# RatDBS.net
KiCad netlist of a schematic drawn in EAGLE
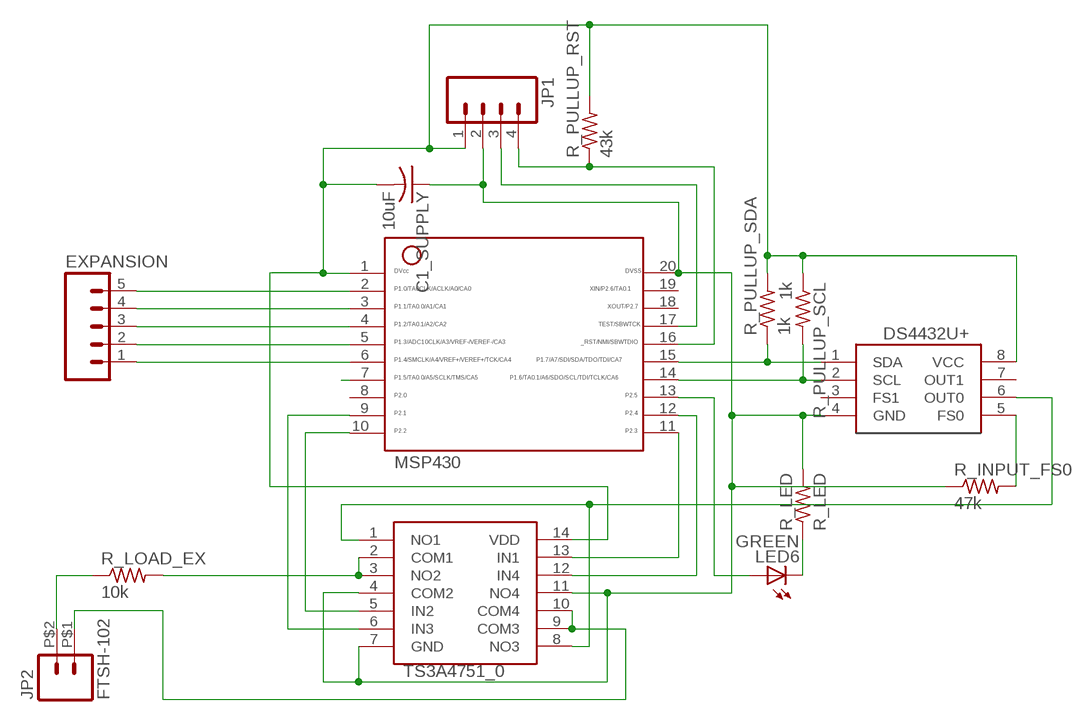
[diagram p0: schematic, sheet 1]

(export (version "E")
  (design (tool "Eeschema 10.0.6"))
  (components
    (comp (ref "C1_SUPPLY")
      (value "10uF")
      (footprint "eagle-import:C0603")
      (libsource (lib "eagle-import") (part "C-USC0603"))
    )
    (comp (ref "DS4432U+")
      (value "DS4432U+")
      (footprint "eagle-import:8_PIN")
      (libsource (lib "eagle-import") (part "DS4432U+"))
    )
    (comp (ref "EXPANSION")
      (value "M051.27MM")
      (footprint "eagle-import:1X05-1.27MM")
      (libsource (lib "eagle-import") (part "M051.27MM"))
    )
    (comp (ref "JP1")
      (value "M041.27MM")
      (footprint "eagle-import:1X04-1.27MM")
      (libsource (lib "eagle-import") (part "M041.27MM"))
    )
    (comp (ref "JP2")
      (value "FTSH-102")
      (footprint "eagle-import:FTSH-102-DH")
      (libsource (lib "eagle-import") (part "FTSH-102"))
    )
    (comp (ref "LED6")
      (value "GREEN")
      (footprint "eagle-import:LED-1206")
      (libsource (lib "eagle-import") (part "LED1206"))
    )
    (comp (ref "MSP430")
      (value "MSP430")
      (footprint "eagle-import:20_PIN")
      (libsource (lib "eagle-import") (part "MSP430"))
    )
    (comp (ref "R_INPUT_FS0")
      (value "47k")
      (footprint "eagle-import:R0603")
      (libsource (lib "eagle-import") (part "R-US_R0603"))
    )
    (comp (ref "R_LED")
      (value "R_LED")
      (footprint "eagle-import:R0603")
      (libsource (lib "eagle-import") (part "R-US_R0603"))
    )
    (comp (ref "R_LOAD_EX")
      (value "10k")
      (footprint "eagle-import:R0603")
      (libsource (lib "eagle-import") (part "R-US_R0603"))
    )
    (comp (ref "R_PULLUP_RST")
      (value "43k")
      (footprint "eagle-import:R0603")
      (libsource (lib "eagle-import") (part "R-US_R0603"))
    )
    (comp (ref "R_PULLUP_SCL")
      (value "1k")
      (footprint "eagle-import:R0603")
      (libsource (lib "eagle-import") (part "R-US_R0603"))
    )
    (comp (ref "R_PULLUP_SDA")
      (value "1k")
      (footprint "eagle-import:R0603")
      (libsource (lib "eagle-import") (part "R-US_R0603"))
    )
    (comp (ref "TS3A4751_0")
      (value "TS3A4751")
      (footprint "eagle-import:14_PIN")
      (libsource (lib "eagle-import") (part "TS3A4751"))
    )
  )
  (nets
    (net (code "1") (name "Net-(DS4432U+-FS0)") (class "Default")
      (node (ref "DS4432U+") (pin "5") (pinfunction "FS0_5") (pintype "bidirectional"))
      (node (ref "R_INPUT_FS0") (pin "2") (pinfunction "2_2") (pintype "passive"))
    )
    (net (code "2") (name "Net-(DS4432U+-GND)") (class "Default")
      (node (ref "C1_SUPPLY") (pin "1") (pinfunction "1_1") (pintype "passive"))
      (node (ref "DS4432U+") (pin "4") (pinfunction "GND_4") (pintype "bidirectional"))
      (node (ref "JP1") (pin "2") (pinfunction "2_2") (pintype "passive"))
      (node (ref "MSP430") (pin "20") (pinfunction "20_20") (pintype "bidirectional"))
      (node (ref "R_INPUT_FS0") (pin "1") (pinfunction "1_1") (pintype "passive"))
      (node (ref "R_LED") (pin "2") (pinfunction "2_2") (pintype "passive"))
      (node (ref "TS3A4751_0") (pin "11") (pinfunction "NO4_11") (pintype "bidirectional"))
      (node (ref "TS3A4751_0") (pin "4") (pinfunction "COM2_4") (pintype "bidirectional"))
      (node (ref "TS3A4751_0") (pin "7") (pinfunction "GND_7") (pintype "bidirectional"))
    )
    (net (code "3") (name "Net-(DS4432U+-OUT0)") (class "Default")
      (node (ref "DS4432U+") (pin "6") (pinfunction "OUT0_6") (pintype "bidirectional"))
      (node (ref "TS3A4751_0") (pin "1") (pinfunction "NO1_1") (pintype "bidirectional"))
      (node (ref "TS3A4751_0") (pin "8") (pinfunction "NO3_8") (pintype "bidirectional"))
    )
    (net (code "4") (name "Net-(DS4432U+-SCL)") (class "Default")
      (node (ref "DS4432U+") (pin "2") (pinfunction "SCL_2") (pintype "bidirectional"))
      (node (ref "MSP430") (pin "14") (pinfunction "14_14") (pintype "bidirectional"))
      (node (ref "R_PULLUP_SCL") (pin "2") (pinfunction "2_2") (pintype "passive"))
    )
    (net (code "5") (name "Net-(DS4432U+-SDA)") (class "Default")
      (node (ref "DS4432U+") (pin "1") (pinfunction "SDA_1") (pintype "bidirectional"))
      (node (ref "MSP430") (pin "15") (pinfunction "15_15") (pintype "bidirectional"))
      (node (ref "R_PULLUP_SDA") (pin "1") (pinfunction "1_1") (pintype "passive"))
    )
    (net (code "6") (name "Net-(DS4432U+-VCC)") (class "Default")
      (node (ref "C1_SUPPLY") (pin "2") (pinfunction "2_2") (pintype "passive"))
      (node (ref "DS4432U+") (pin "8") (pinfunction "VCC_8") (pintype "bidirectional"))
      (node (ref "JP1") (pin "1") (pinfunction "1_1") (pintype "passive"))
      (node (ref "MSP430") (pin "1") (pinfunction "1_1") (pintype "bidirectional"))
      (node (ref "R_PULLUP_RST") (pin "2") (pinfunction "2_2") (pintype "passive"))
      (node (ref "R_PULLUP_SCL") (pin "1") (pinfunction "1_1") (pintype "passive"))
      (node (ref "R_PULLUP_SDA") (pin "2") (pinfunction "2_2") (pintype "passive"))
      (node (ref "TS3A4751_0") (pin "14") (pinfunction "VDD_14") (pintype "bidirectional"))
    )
    (net (code "7") (name "Net-(EXPANSION-Pad1)") (class "Default")
      (node (ref "EXPANSION") (pin "1") (pinfunction "1_1") (pintype "passive"))
      (node (ref "MSP430") (pin "6") (pinfunction "6_6") (pintype "bidirectional"))
    )
    (net (code "8") (name "Net-(EXPANSION-Pad2)") (class "Default")
      (node (ref "EXPANSION") (pin "2") (pinfunction "2_2") (pintype "passive"))
      (node (ref "MSP430") (pin "5") (pinfunction "5_5") (pintype "bidirectional"))
    )
    (net (code "9") (name "Net-(EXPANSION-Pad3)") (class "Default")
      (node (ref "EXPANSION") (pin "3") (pinfunction "3_3") (pintype "passive"))
      (node (ref "MSP430") (pin "4") (pinfunction "4_4") (pintype "bidirectional"))
    )
    (net (code "10") (name "Net-(EXPANSION-Pad4)") (class "Default")
      (node (ref "EXPANSION") (pin "4") (pinfunction "4_4") (pintype "passive"))
      (node (ref "MSP430") (pin "3") (pinfunction "3_3") (pintype "bidirectional"))
    )
    (net (code "11") (name "Net-(EXPANSION-Pad5)") (class "Default")
      (node (ref "EXPANSION") (pin "5") (pinfunction "5_5") (pintype "passive"))
      (node (ref "MSP430") (pin "2") (pinfunction "2_2") (pintype "bidirectional"))
    )
    (net (code "12") (name "Net-(JP1-Pad3)") (class "Default")
      (node (ref "JP1") (pin "3") (pinfunction "3_3") (pintype "passive"))
      (node (ref "MSP430") (pin "17") (pinfunction "17_17") (pintype "bidirectional"))
    )
    (net (code "13") (name "Net-(JP1-Pad4)") (class "Default")
      (node (ref "JP1") (pin "4") (pinfunction "4_4") (pintype "passive"))
      (node (ref "MSP430") (pin "16") (pinfunction "16_16") (pintype "bidirectional"))
      (node (ref "R_PULLUP_RST") (pin "1") (pinfunction "1_1") (pintype "passive"))
    )
    (net (code "14") (name "Net-(JP2-1)") (class "Default")
      (node (ref "JP2") (pin "P$1") (pinfunction "1_P$1") (pintype "passive"))
      (node (ref "TS3A4751_0") (pin "10") (pinfunction "COM4_10") (pintype "bidirectional"))
      (node (ref "TS3A4751_0") (pin "9") (pinfunction "COM3_9") (pintype "bidirectional"))
    )
    (net (code "15") (name "Net-(JP2-2)") (class "Default")
      (node (ref "JP2") (pin "P$2") (pinfunction "2_P$2") (pintype "passive"))
      (node (ref "R_LOAD_EX") (pin "1") (pinfunction "1_1") (pintype "passive"))
    )
    (net (code "16") (name "Net-(LED6-PadA)") (class "Default")
      (node (ref "LED6") (pin "A") (pinfunction "A_A") (pintype "passive"))
      (node (ref "MSP430") (pin "13") (pinfunction "13_13") (pintype "bidirectional"))
    )
    (net (code "17") (name "Net-(LED6-PadC)") (class "Default")
      (node (ref "LED6") (pin "C") (pinfunction "C_C") (pintype "passive"))
      (node (ref "R_LED") (pin "1") (pinfunction "1_1") (pintype "passive"))
    )
    (net (code "18") (name "Net-(TS3A4751_0-COM1)") (class "Default")
      (node (ref "R_LOAD_EX") (pin "2") (pinfunction "2_2") (pintype "passive"))
      (node (ref "TS3A4751_0") (pin "2") (pinfunction "COM1_2") (pintype "bidirectional"))
      (node (ref "TS3A4751_0") (pin "3") (pinfunction "NO2_3") (pintype "bidirectional"))
    )
    (net (code "19") (name "Net-(TS3A4751_0-IN1)") (class "Default")
      (node (ref "MSP430") (pin "11") (pinfunction "11_11") (pintype "bidirectional"))
      (node (ref "TS3A4751_0") (pin "13") (pinfunction "IN1_13") (pintype "bidirectional"))
    )
    (net (code "20") (name "Net-(TS3A4751_0-IN2)") (class "Default")
      (node (ref "MSP430") (pin "10") (pinfunction "10_10") (pintype "bidirectional"))
      (node (ref "TS3A4751_0") (pin "5") (pinfunction "IN2_5") (pintype "bidirectional"))
    )
    (net (code "21") (name "Net-(TS3A4751_0-IN3)") (class "Default")
      (node (ref "MSP430") (pin "9") (pinfunction "9_9") (pintype "bidirectional"))
      (node (ref "TS3A4751_0") (pin "6") (pinfunction "IN3_6") (pintype "bidirectional"))
    )
    (net (code "22") (name "Net-(TS3A4751_0-IN4)") (class "Default")
      (node (ref "MSP430") (pin "12") (pinfunction "12_12") (pintype "bidirectional"))
      (node (ref "TS3A4751_0") (pin "12") (pinfunction "IN4_12") (pintype "bidirectional"))
    )
    (net (code "23") (name "unconnected-(DS4432U+-FS1-Pad3)") (class "Default")
      (node (ref "DS4432U+") (pin "3") (pinfunction "FS1_3") (pintype "bidirectional"))
    )
    (net (code "24") (name "unconnected-(DS4432U+-OUT1-Pad7)") (class "Default")
      (node (ref "DS4432U+") (pin "7") (pinfunction "OUT1_7") (pintype "bidirectional"))
    )
    (net (code "25") (name "unconnected-(MSP430-Pad7)") (class "Default")
      (node (ref "MSP430") (pin "7") (pinfunction "7_7") (pintype "bidirectional"))
    )
    (net (code "26") (name "unconnected-(MSP430-Pad8)") (class "Default")
      (node (ref "MSP430") (pin "8") (pinfunction "8_8") (pintype "bidirectional"))
    )
    (net (code "27") (name "unconnected-(MSP430-Pad18)") (class "Default")
      (node (ref "MSP430") (pin "18") (pinfunction "18_18") (pintype "bidirectional"))
    )
    (net (code "28") (name "unconnected-(MSP430-Pad19)") (class "Default")
      (node (ref "MSP430") (pin "19") (pinfunction "19_19") (pintype "bidirectional"))
    )
  )
)
